# LaunchPadMikroBUS_SIL.net
KiCad netlist of a schematic drawn in EAGLE
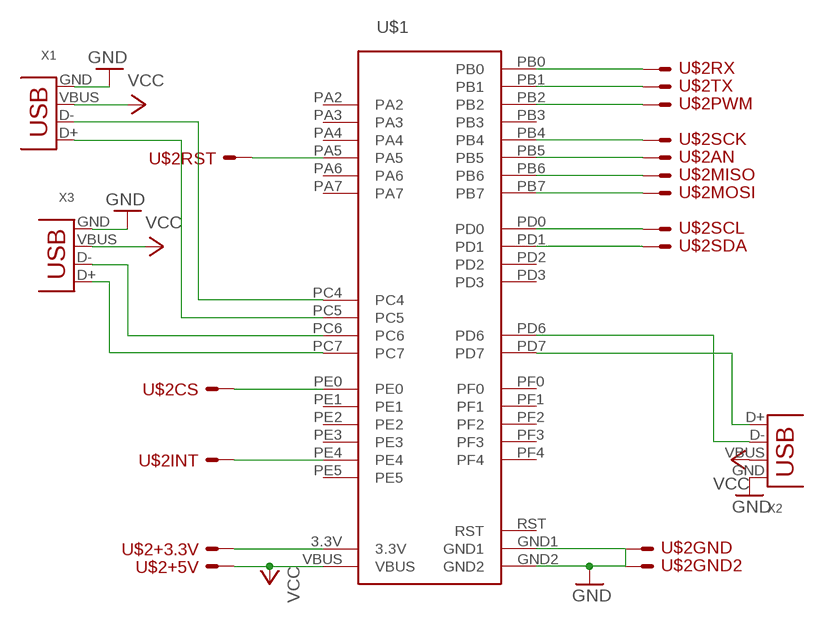
[diagram p0: schematic, sheet 1]

(export (version "E")
  (design (tool "Eeschema 10.0.6"))
  (components
    (comp (ref "U$1")
      (value "STELLARIS-LAUNCHPADSTELLARIS-LAUNCHPAD-XL")
      (footprint "eagle-import:LAUNCHPAD-XL")
      (libsource (lib "eagle-import") (part "STELLARIS-LAUNCHPADSTELLARIS-LAUNCHPAD-XL"))
    )
    (comp (ref "U$2")
      (value "MIKROBUSSIL")
      (footprint "eagle-import:MIKROBUS_SIL")
      (libsource (lib "eagle-import") (part "MIKROBUSSIL"))
    )
    (comp (ref "X1")
      (value "USB-A-H")
      (footprint "eagle-import:USB-A-H")
      (libsource (lib "eagle-import") (part "USB-A-H"))
    )
    (comp (ref "X2")
      (value "USB-A-H")
      (footprint "eagle-import:USB-A-H")
      (libsource (lib "eagle-import") (part "USB-A-H"))
    )
    (comp (ref "X3")
      (value "USB-A-H")
      (footprint "eagle-import:USB-A-H")
      (libsource (lib "eagle-import") (part "USB-A-H"))
    )
  )
  (nets
    (net (code "1") (name "/RST") (class "Default")
      (node (ref "U$1") (pin "RST") (pinfunction "RST_RST") (pintype "power_in"))
    )
    (net (code "2") (name "GND") (class "Default")
      (node (ref "U$1") (pin "GND1") (pinfunction "GND1_GND1") (pintype "bidirectional"))
      (node (ref "U$1") (pin "GND2") (pinfunction "GND2_GND2") (pintype "power_in"))
      (node (ref "U$2") (pin "GND") (pinfunction "S_GND") (pintype "passive"))
      (node (ref "U$2") (pin "GND2") (pinfunction "S_GND2") (pintype "passive"))
      (node (ref "X1") (pin "GND") (pinfunction "GND_GND") (pintype "bidirectional"))
      (node (ref "X2") (pin "GND") (pinfunction "GND_GND") (pintype "bidirectional"))
      (node (ref "X3") (pin "GND") (pinfunction "GND_GND") (pintype "bidirectional"))
    )
    (net (code "3") (name "Net-(U$1-PadPC4)") (class "Default")
      (node (ref "U$1") (pin "PC4") (pinfunction "PC4_PC4") (pintype "bidirectional"))
      (node (ref "X1") (pin "D-") (pinfunction "D-_D-") (pintype "bidirectional"))
    )
    (net (code "4") (name "Net-(U$1-PadPC5)") (class "Default")
      (node (ref "U$1") (pin "PC5") (pinfunction "PC5_PC5") (pintype "bidirectional"))
      (node (ref "X1") (pin "D+") (pinfunction "D+_D+") (pintype "bidirectional"))
    )
    (net (code "5") (name "Net-(U$1-PadPC6)") (class "Default")
      (node (ref "U$1") (pin "PC6") (pinfunction "PC6_PC6") (pintype "bidirectional"))
      (node (ref "X3") (pin "D-") (pinfunction "D-_D-") (pintype "bidirectional"))
    )
    (net (code "6") (name "Net-(U$1-PadPC7)") (class "Default")
      (node (ref "U$1") (pin "PC7") (pinfunction "PC7_PC7") (pintype "bidirectional"))
      (node (ref "X3") (pin "D+") (pinfunction "D+_D+") (pintype "bidirectional"))
    )
    (net (code "7") (name "Net-(U$1-PadPD6)") (class "Default")
      (node (ref "U$1") (pin "PD6") (pinfunction "PD6_PD6") (pintype "bidirectional"))
      (node (ref "X2") (pin "D-") (pinfunction "D-_D-") (pintype "bidirectional"))
    )
    (net (code "8") (name "Net-(U$1-PadPD7)") (class "Default")
      (node (ref "U$1") (pin "PD7") (pinfunction "PD7_PD7") (pintype "bidirectional"))
      (node (ref "X2") (pin "D+") (pinfunction "D+_D+") (pintype "bidirectional"))
    )
    (net (code "9") (name "Net-(U$2A-S)") (class "Default")
      (node (ref "U$1") (pin "3.3V") (pinfunction "3.3V_3.3V") (pintype "power_in"))
      (node (ref "U$2") (pin "+3.3V") (pinfunction "S_+3.3V") (pintype "passive"))
    )
    (net (code "10") (name "Net-(U$2C-S)") (class "Default")
      (node (ref "U$1") (pin "PB5") (pinfunction "PB5_PB5") (pintype "bidirectional"))
      (node (ref "U$2") (pin "AN") (pinfunction "S_AN") (pintype "passive"))
    )
    (net (code "11") (name "Net-(U$2D-S)") (class "Default")
      (node (ref "U$1") (pin "PE0") (pinfunction "PE0_PE0") (pintype "bidirectional"))
      (node (ref "U$2") (pin "CS") (pinfunction "S_CS") (pintype "passive"))
    )
    (net (code "12") (name "Net-(U$2G-S)") (class "Default")
      (node (ref "U$1") (pin "PE4") (pinfunction "PE4_PE4") (pintype "bidirectional"))
      (node (ref "U$2") (pin "INT") (pinfunction "S_INT") (pintype "passive"))
    )
    (net (code "13") (name "Net-(U$2H-S)") (class "Default")
      (node (ref "U$1") (pin "PB6") (pinfunction "PB6_PB6") (pintype "bidirectional"))
      (node (ref "U$2") (pin "MISO") (pinfunction "S_MISO") (pintype "passive"))
    )
    (net (code "14") (name "Net-(U$2I-S)") (class "Default")
      (node (ref "U$1") (pin "PB7") (pinfunction "PB7_PB7") (pintype "bidirectional"))
      (node (ref "U$2") (pin "MOSI") (pinfunction "S_MOSI") (pintype "passive"))
    )
    (net (code "15") (name "Net-(U$2J-S)") (class "Default")
      (node (ref "U$1") (pin "PB2") (pinfunction "PB2_PB2") (pintype "bidirectional"))
      (node (ref "U$2") (pin "PWM") (pinfunction "S_PWM") (pintype "passive"))
    )
    (net (code "16") (name "Net-(U$2K-S)") (class "Default")
      (node (ref "U$1") (pin "PA5") (pinfunction "PA5_PA5") (pintype "bidirectional"))
      (node (ref "U$2") (pin "RST") (pinfunction "S_RST") (pintype "passive"))
    )
    (net (code "17") (name "Net-(U$2L-S)") (class "Default")
      (node (ref "U$1") (pin "PB0") (pinfunction "PB0_PB0") (pintype "bidirectional"))
      (node (ref "U$2") (pin "RX") (pinfunction "S_RX") (pintype "passive"))
    )
    (net (code "18") (name "Net-(U$2M-S)") (class "Default")
      (node (ref "U$1") (pin "PB4") (pinfunction "PB4_PB4") (pintype "bidirectional"))
      (node (ref "U$2") (pin "SCK") (pinfunction "S_SCK") (pintype "passive"))
    )
    (net (code "19") (name "Net-(U$2N-S)") (class "Default")
      (node (ref "U$1") (pin "PD0") (pinfunction "PD0_PD0") (pintype "bidirectional"))
      (node (ref "U$2") (pin "SCL") (pinfunction "S_SCL") (pintype "passive"))
    )
    (net (code "20") (name "Net-(U$2O-S)") (class "Default")
      (node (ref "U$1") (pin "PD1") (pinfunction "PD1_PD1") (pintype "bidirectional"))
      (node (ref "U$2") (pin "SDA") (pinfunction "S_SDA") (pintype "passive"))
    )
    (net (code "21") (name "Net-(U$2P-S)") (class "Default")
      (node (ref "U$1") (pin "PB1") (pinfunction "PB1_PB1") (pintype "bidirectional"))
      (node (ref "U$2") (pin "TX") (pinfunction "S_TX") (pintype "passive"))
    )
    (net (code "22") (name "VCC") (class "Default")
      (node (ref "U$1") (pin "VBUS") (pinfunction "VBUS_VBUS") (pintype "power_in"))
      (node (ref "U$2") (pin "+5V") (pinfunction "S_+5V") (pintype "passive"))
      (node (ref "X1") (pin "VBUS") (pinfunction "VBUS_VBUS") (pintype "bidirectional"))
      (node (ref "X2") (pin "VBUS") (pinfunction "VBUS_VBUS") (pintype "bidirectional"))
      (node (ref "X3") (pin "VBUS") (pinfunction "VBUS_VBUS") (pintype "bidirectional"))
    )
    (net (code "23") (name "unconnected-(U$1-PadPA2)") (class "Default")
      (node (ref "U$1") (pin "PA2") (pinfunction "PA2_PA2") (pintype "bidirectional"))
    )
    (net (code "24") (name "unconnected-(U$1-PadPA3)") (class "Default")
      (node (ref "U$1") (pin "PA3") (pinfunction "PA3_PA3") (pintype "bidirectional"))
    )
    (net (code "25") (name "unconnected-(U$1-PadPA4)") (class "Default")
      (node (ref "U$1") (pin "PA4") (pinfunction "PA4_PA4") (pintype "bidirectional"))
    )
    (net (code "26") (name "unconnected-(U$1-PadPA6)") (class "Default")
      (node (ref "U$1") (pin "PA6") (pinfunction "PA6_PA6") (pintype "bidirectional"))
    )
    (net (code "27") (name "unconnected-(U$1-PadPA7)") (class "Default")
      (node (ref "U$1") (pin "PA7") (pinfunction "PA7_PA7") (pintype "bidirectional"))
    )
    (net (code "28") (name "unconnected-(U$1-PadPB3)") (class "Default")
      (node (ref "U$1") (pin "PB3") (pinfunction "PB3_PB3") (pintype "bidirectional"))
    )
    (net (code "29") (name "unconnected-(U$1-PadPD2)") (class "Default")
      (node (ref "U$1") (pin "PD2") (pinfunction "PD2_PD2") (pintype "bidirectional"))
    )
    (net (code "30") (name "unconnected-(U$1-PadPD3)") (class "Default")
      (node (ref "U$1") (pin "PD3") (pinfunction "PD3_PD3") (pintype "bidirectional"))
    )
    (net (code "31") (name "unconnected-(U$1-PadPE1)") (class "Default")
      (node (ref "U$1") (pin "PE1") (pinfunction "PE1_PE1") (pintype "bidirectional"))
    )
    (net (code "32") (name "unconnected-(U$1-PadPE2)") (class "Default")
      (node (ref "U$1") (pin "PE2") (pinfunction "PE2_PE2") (pintype "bidirectional"))
    )
    (net (code "33") (name "unconnected-(U$1-PadPE3)") (class "Default")
      (node (ref "U$1") (pin "PE3") (pinfunction "PE3_PE3") (pintype "bidirectional"))
    )
    (net (code "34") (name "unconnected-(U$1-PadPE5)") (class "Default")
      (node (ref "U$1") (pin "PE5") (pinfunction "PE5_PE5") (pintype "bidirectional"))
    )
    (net (code "35") (name "unconnected-(U$1-PadPF0)") (class "Default")
      (node (ref "U$1") (pin "PF0") (pinfunction "PF0_PF0") (pintype "bidirectional"))
    )
    (net (code "36") (name "unconnected-(U$1-PadPF1)") (class "Default")
      (node (ref "U$1") (pin "PF1") (pinfunction "PF1_PF1") (pintype "bidirectional"))
    )
    (net (code "37") (name "unconnected-(U$1-PadPF2)") (class "Default")
      (node (ref "U$1") (pin "PF2") (pinfunction "PF2_PF2") (pintype "bidirectional"))
    )
    (net (code "38") (name "unconnected-(U$1-PadPF3)") (class "Default")
      (node (ref "U$1") (pin "PF3") (pinfunction "PF3_PF3") (pintype "bidirectional"))
    )
    (net (code "39") (name "unconnected-(U$1-PadPF4)") (class "Default")
      (node (ref "U$1") (pin "PF4") (pinfunction "PF4_PF4") (pintype "bidirectional"))
    )
  )
)
